# voltage_monitor_rev_1.net
KiCad netlist of a schematic drawn in Altium Designer
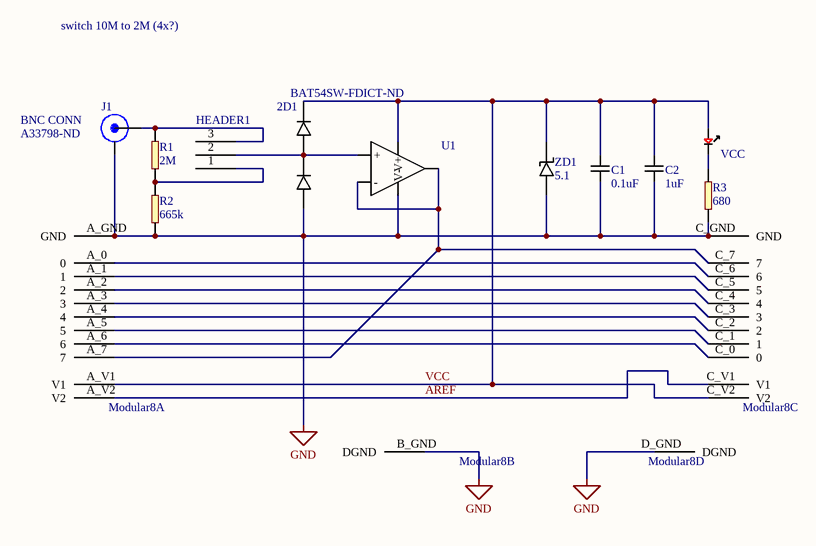
[diagram p0: voltage_monitor_rev_1.SchDoc]

(export (version "E")
  (design (tool "Eeschema 10.0.6"))
  (components
    (comp (ref "2D1")
      (value "BAT54SW-FDICT")
      (footprint "SOT-23-3")
      (fields (field (name "SUPPLIER PART NUMBER 1") "BAT54SW-FDICT-ND"))
      (libsource (lib "OpBots") (part "BAT54SW-FDICT"))
    )
    (comp (ref "C1")
      (value "Capacitor")
      (footprint "0603")
      (fields (field (name "C") "0.1uF"))
      (libsource (lib "OpBots") (part "Capacitor"))
    )
    (comp (ref "C2")
      (value "Capacitor")
      (footprint "0603")
      (fields (field (name "C") "1uF"))
      (libsource (lib "OpBots") (part "Capacitor"))
    )
    (comp (ref "HEADER1")
      (value "3x1")
      (footprint "3x1 THRU HOLES 0.1\" PITCH")
      (libsource (lib "OpBots") (part "3x1"))
    )
    (comp (ref "J1")
      (value "BNC CONN")
      (footprint "BNC THROUGH HOLE")
      (fields (field (name "SUPPLIER PART NUMBER 1") "A33798-ND"))
      (libsource (lib "OpBots") (part "A33798"))
    )
    (comp (ref "Modular8")
      (value "modular8_rev2_A&C")
      (footprint "modular8 edges A & C")
      (libsource (lib "OpBots") (part "modular8_rev2_A&C"))
    )
    (comp (ref "R1")
      (value "R 2M 1%")
      (footprint "0603")
      (fields (field (name "R") "2M"))
      (libsource (lib "RLC") (part "R 2M 1%"))
    )
    (comp (ref "R2")
      (value "R 665k 1%")
      (footprint "0603")
      (fields (field (name "R") "665k"))
      (libsource (lib "RLC") (part "R 665k 1%"))
    )
    (comp (ref "R3")
      (value "Resistor")
      (footprint "0603")
      (fields (field (name "R") "680"))
      (libsource (lib "OpBots") (part "Resistor"))
    )
    (comp (ref "U1") (value "MCP6001") (footprint "SOT-23-5") (libsource (lib "OpBots") (part "MCP6001")))
    (comp (ref "VCC") (value "LEDY") (footprint "0805 - LED") (libsource (lib "OpBots") (part "LEDY")))
    (comp (ref "ZD1")
      (value "Zener 5.1V")
      (footprint "SOD-323F")
      (fields (field (name "VOLTAGE") "5.1"))
      (libsource (lib "OpBots") (part "Zener 5.1V"))
    )
  )
  (nets
    (net (code "1") (name "/AREF") (class "Default")
      (node (ref "Modular8") (pin "A_V2") (pinfunction "V2_A_V2") (pintype "passive"))
      (node (ref "Modular8") (pin "C_V1") (pinfunction "V1_C_V1") (pintype "passive"))
    )
    (net (code "2") (name "/VCC") (class "Default")
      (node (ref "2D1") (pin "2") (pintype "passive"))
      (node (ref "C1") (pin "1") (pintype "passive"))
      (node (ref "C2") (pin "1") (pintype "passive"))
      (node (ref "Modular8") (pin "A_V1") (pinfunction "V1_A_V1") (pintype "passive"))
      (node (ref "Modular8") (pin "C_V2") (pinfunction "V2_C_V2") (pintype "passive"))
      (node (ref "U1") (pin "5") (pinfunction "V+_5") (pintype "passive"))
      (node (ref "VCC") (pin "1") (pinfunction "A_1") (pintype "passive"))
      (node (ref "ZD1") (pin "1") (pinfunction "1_1") (pintype "passive"))
    )
    (net (code "3") (name "GND") (class "Default")
      (node (ref "2D1") (pin "1") (pintype "passive"))
      (node (ref "C1") (pin "2") (pintype "passive"))
      (node (ref "C2") (pin "2") (pintype "passive"))
      (node (ref "J1") (pin "1") (pinfunction "G_1") (pintype "passive"))
      (node (ref "Modular8") (pin "A_GND") (pinfunction "GND_A_GND") (pintype "passive"))
      (node (ref "Modular8") (pin "B_GND") (pinfunction "DGND_B_GND") (pintype "passive"))
      (node (ref "Modular8") (pin "C_GND") (pinfunction "GND_C_GND") (pintype "passive"))
      (node (ref "Modular8") (pin "D_GND") (pinfunction "DGND_D_GND") (pintype "passive"))
      (node (ref "R2") (pin "2") (pintype "passive"))
      (node (ref "R3") (pin "2") (pintype "passive"))
      (node (ref "U1") (pin "2") (pinfunction "V-_2") (pintype "passive"))
      (node (ref "ZD1") (pin "2") (pinfunction "2_2") (pintype "passive"))
    )
    (net (code "4") (name "Net-(HEADER1-Pad1)") (class "Default")
      (node (ref "HEADER1") (pin "1") (pintype "passive"))
      (node (ref "R1") (pin "2") (pintype "passive"))
      (node (ref "R2") (pin "1") (pintype "passive"))
    )
    (net (code "5") (name "Net-(J1-S)") (class "Default")
      (node (ref "HEADER1") (pin "3") (pintype "passive"))
      (node (ref "J1") (pin "2") (pinfunction "S_2") (pintype "passive"))
      (node (ref "R1") (pin "1") (pintype "passive"))
    )
    (net (code "6") (name "Net-(Modular8A-0)") (class "Default")
      (node (ref "Modular8") (pin "A_0") (pinfunction "0_A_0") (pintype "passive"))
      (node (ref "Modular8") (pin "C_6") (pinfunction "6_C_6") (pintype "passive"))
    )
    (net (code "7") (name "Net-(Modular8A-1)") (class "Default")
      (node (ref "Modular8") (pin "A_1") (pinfunction "1_A_1") (pintype "passive"))
      (node (ref "Modular8") (pin "C_5") (pinfunction "5_C_5") (pintype "passive"))
    )
    (net (code "8") (name "Net-(Modular8A-2)") (class "Default")
      (node (ref "Modular8") (pin "A_2") (pinfunction "2_A_2") (pintype "passive"))
      (node (ref "Modular8") (pin "C_4") (pinfunction "4_C_4") (pintype "passive"))
    )
    (net (code "9") (name "Net-(Modular8A-3)") (class "Default")
      (node (ref "Modular8") (pin "A_3") (pinfunction "3_A_3") (pintype "passive"))
      (node (ref "Modular8") (pin "C_3") (pinfunction "3_C_3") (pintype "passive"))
    )
    (net (code "10") (name "Net-(Modular8A-4)") (class "Default")
      (node (ref "Modular8") (pin "A_4") (pinfunction "4_A_4") (pintype "passive"))
      (node (ref "Modular8") (pin "C_2") (pinfunction "2_C_2") (pintype "passive"))
    )
    (net (code "11") (name "Net-(Modular8A-5)") (class "Default")
      (node (ref "Modular8") (pin "A_5") (pinfunction "5_A_5") (pintype "passive"))
      (node (ref "Modular8") (pin "C_1") (pinfunction "1_C_1") (pintype "passive"))
    )
    (net (code "12") (name "Net-(Modular8A-6)") (class "Default")
      (node (ref "Modular8") (pin "A_6") (pinfunction "6_A_6") (pintype "passive"))
      (node (ref "Modular8") (pin "C_0") (pinfunction "0_C_0") (pintype "passive"))
    )
    (net (code "13") (name "Net-(Modular8A-7)") (class "Default")
      (node (ref "Modular8") (pin "A_7") (pinfunction "7_A_7") (pintype "passive"))
      (node (ref "Modular8") (pin "C_7") (pinfunction "7_C_7") (pintype "passive"))
      (node (ref "U1") (pin "1") (pinfunction "OUT_1") (pintype "passive"))
      (node (ref "U1") (pin "4") (pinfunction "-_4") (pintype "passive"))
    )
    (net (code "14") (name "Net-(U1-+)") (class "Default")
      (node (ref "2D1") (pin "3") (pintype "passive"))
      (node (ref "HEADER1") (pin "2") (pintype "passive"))
      (node (ref "U1") (pin "3") (pinfunction "+_3") (pintype "passive"))
    )
    (net (code "15") (name "Net-(VCC-K)") (class "Default")
      (node (ref "R3") (pin "1") (pintype "passive"))
      (node (ref "VCC") (pin "2") (pinfunction "K_2") (pintype "passive"))
    )
  )
)
